# schematic.net
KiCad netlist of a schematic drawn in EAGLE
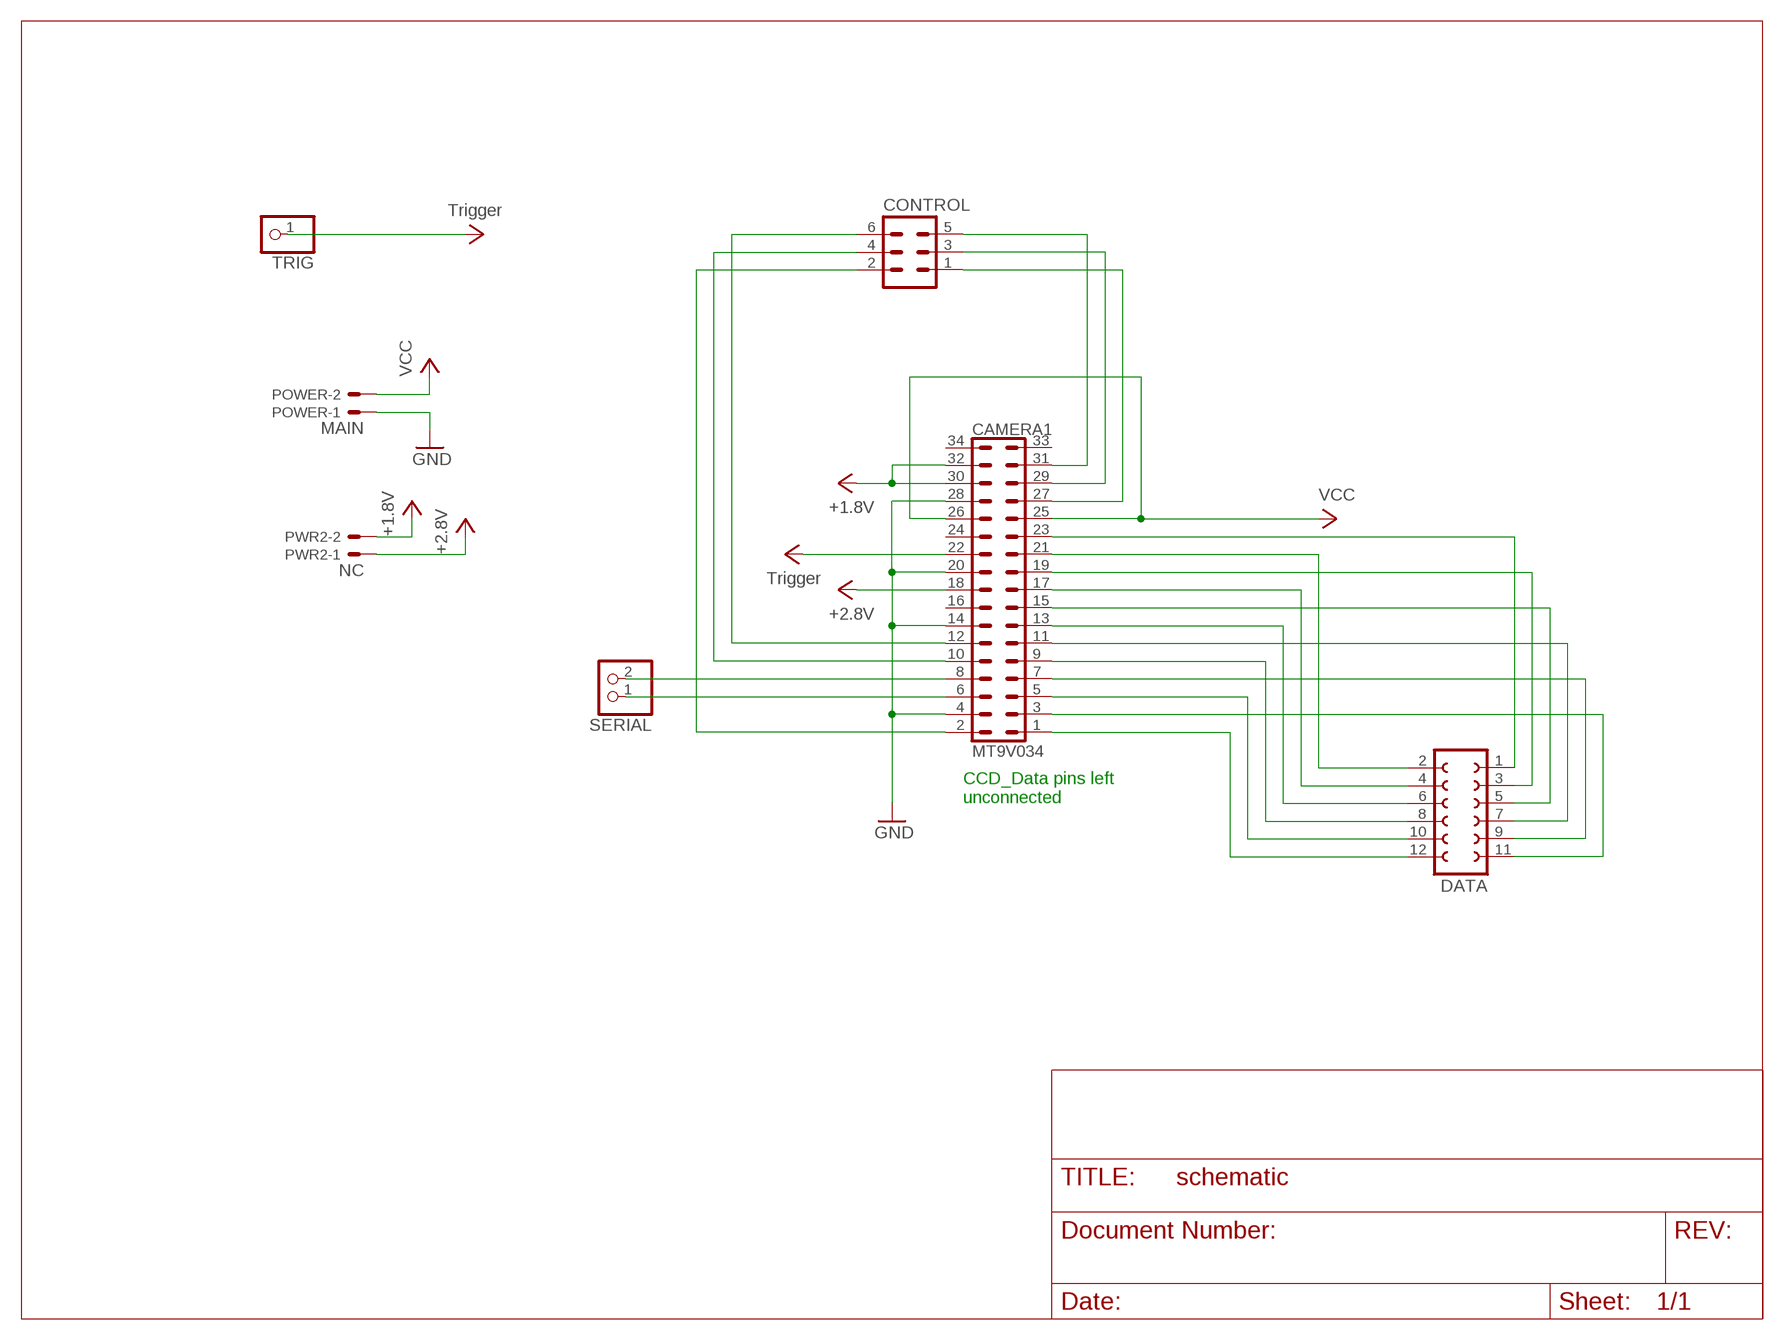
[diagram p0: schematic, sheet 1]

(export (version "E")
  (design (tool "Eeschema 10.0.6"))
  (components
    (comp (ref "CAMERA1")
      (value "MT9V034")
      (footprint "eagle-import:PHB_1MM27_2X17_SNT")
      (libsource (lib "eagle-import") (part "PHB_1MM27_2X17_SNT"))
    )
    (comp (ref "CONTROL")
      (value "MA03-2")
      (footprint "eagle-import:MA03-2")
      (libsource (lib "eagle-import") (part "MA03-2"))
    )
    (comp (ref "DATA")
      (value "FE06-2")
      (footprint "eagle-import:FE06-2")
      (libsource (lib "eagle-import") (part "FE06-2"))
    )
    (comp (ref "POWER")
      (value "MAIN")
      (footprint "eagle-import:22-23-2021")
      (fields (field (name "MF") "MOLEX") (field (name "MPN") "22-23-2021"))
      (libsource (lib "eagle-import") (part "22-23-2021"))
    )
    (comp (ref "PWR2")
      (value "NC")
      (footprint "eagle-import:22-23-2021")
      (fields (field (name "MF") "MOLEX") (field (name "MPN") "22-23-2021"))
      (libsource (lib "eagle-import") (part "22-23-2021"))
    )
    (comp (ref "SERIAL")
      (value "PINHD-1X2")
      (footprint "eagle-import:1X02")
      (libsource (lib "eagle-import") (part "PINHD-1X2"))
    )
    (comp (ref "TRIG")
      (value "PINHD-1X1")
      (footprint "eagle-import:1X01")
      (libsource (lib "eagle-import") (part "PINHD-1X1"))
    )
  )
  (nets
    (net (code "1") (name "+1.8V") (class "Default")
      (node (ref "CAMERA1") (pin "30") (pinfunction "30_30") (pintype "passive"))
      (node (ref "CAMERA1") (pin "32") (pinfunction "32_32") (pintype "passive"))
      (node (ref "PWR2") (pin "2") (pinfunction "S_2") (pintype "passive"))
    )
    (net (code "2") (name "+2.8V") (class "Default")
      (node (ref "CAMERA1") (pin "18") (pinfunction "18_18") (pintype "passive"))
      (node (ref "PWR2") (pin "1") (pinfunction "S_1") (pintype "passive"))
    )
    (net (code "3") (name "GND") (class "Default")
      (node (ref "CAMERA1") (pin "14") (pinfunction "14_14") (pintype "passive"))
      (node (ref "CAMERA1") (pin "20") (pinfunction "20_20") (pintype "passive"))
      (node (ref "CAMERA1") (pin "28") (pinfunction "28_28") (pintype "passive"))
      (node (ref "CAMERA1") (pin "4") (pinfunction "4_4") (pintype "passive"))
      (node (ref "POWER") (pin "1") (pinfunction "S_1") (pintype "passive"))
    )
    (net (code "4") (name "Net-(CAMERA1-Pad1)") (class "Default")
      (node (ref "CAMERA1") (pin "1") (pinfunction "1_1") (pintype "passive"))
      (node (ref "DATA") (pin "12") (pinfunction "12_12") (pintype "passive"))
    )
    (net (code "5") (name "Net-(CAMERA1-Pad2)") (class "Default")
      (node (ref "CAMERA1") (pin "2") (pinfunction "2_2") (pintype "passive"))
      (node (ref "CONTROL") (pin "2") (pinfunction "2_2") (pintype "passive"))
    )
    (net (code "6") (name "Net-(CAMERA1-Pad3)") (class "Default")
      (node (ref "CAMERA1") (pin "3") (pinfunction "3_3") (pintype "passive"))
      (node (ref "DATA") (pin "11") (pinfunction "11_11") (pintype "passive"))
    )
    (net (code "7") (name "Net-(CAMERA1-Pad5)") (class "Default")
      (node (ref "CAMERA1") (pin "5") (pinfunction "5_5") (pintype "passive"))
      (node (ref "DATA") (pin "10") (pinfunction "10_10") (pintype "passive"))
    )
    (net (code "8") (name "Net-(CAMERA1-Pad6)") (class "Default")
      (node (ref "CAMERA1") (pin "6") (pinfunction "6_6") (pintype "passive"))
      (node (ref "SERIAL") (pin "1") (pinfunction "1_1") (pintype "passive"))
    )
    (net (code "9") (name "Net-(CAMERA1-Pad7)") (class "Default")
      (node (ref "CAMERA1") (pin "7") (pinfunction "7_7") (pintype "passive"))
      (node (ref "DATA") (pin "9") (pinfunction "9_9") (pintype "passive"))
    )
    (net (code "10") (name "Net-(CAMERA1-Pad8)") (class "Default")
      (node (ref "CAMERA1") (pin "8") (pinfunction "8_8") (pintype "passive"))
      (node (ref "SERIAL") (pin "2") (pinfunction "2_2") (pintype "passive"))
    )
    (net (code "11") (name "Net-(CAMERA1-Pad9)") (class "Default")
      (node (ref "CAMERA1") (pin "9") (pinfunction "9_9") (pintype "passive"))
      (node (ref "DATA") (pin "8") (pinfunction "8_8") (pintype "passive"))
    )
    (net (code "12") (name "Net-(CAMERA1-Pad10)") (class "Default")
      (node (ref "CAMERA1") (pin "10") (pinfunction "10_10") (pintype "passive"))
      (node (ref "CONTROL") (pin "4") (pinfunction "4_4") (pintype "passive"))
    )
    (net (code "13") (name "Net-(CAMERA1-Pad11)") (class "Default")
      (node (ref "CAMERA1") (pin "11") (pinfunction "11_11") (pintype "passive"))
      (node (ref "DATA") (pin "7") (pinfunction "7_7") (pintype "passive"))
    )
    (net (code "14") (name "Net-(CAMERA1-Pad12)") (class "Default")
      (node (ref "CAMERA1") (pin "12") (pinfunction "12_12") (pintype "passive"))
      (node (ref "CONTROL") (pin "6") (pinfunction "6_6") (pintype "passive"))
    )
    (net (code "15") (name "Net-(CAMERA1-Pad13)") (class "Default")
      (node (ref "CAMERA1") (pin "13") (pinfunction "13_13") (pintype "passive"))
      (node (ref "DATA") (pin "6") (pinfunction "6_6") (pintype "passive"))
    )
    (net (code "16") (name "Net-(CAMERA1-Pad15)") (class "Default")
      (node (ref "CAMERA1") (pin "15") (pinfunction "15_15") (pintype "passive"))
      (node (ref "DATA") (pin "5") (pinfunction "5_5") (pintype "passive"))
    )
    (net (code "17") (name "Net-(CAMERA1-Pad17)") (class "Default")
      (node (ref "CAMERA1") (pin "17") (pinfunction "17_17") (pintype "passive"))
      (node (ref "DATA") (pin "4") (pinfunction "4_4") (pintype "passive"))
    )
    (net (code "18") (name "Net-(CAMERA1-Pad19)") (class "Default")
      (node (ref "CAMERA1") (pin "19") (pinfunction "19_19") (pintype "passive"))
      (node (ref "DATA") (pin "3") (pinfunction "3_3") (pintype "passive"))
    )
    (net (code "19") (name "Net-(CAMERA1-Pad21)") (class "Default")
      (node (ref "CAMERA1") (pin "21") (pinfunction "21_21") (pintype "passive"))
      (node (ref "DATA") (pin "2") (pinfunction "2_2") (pintype "passive"))
    )
    (net (code "20") (name "Net-(CAMERA1-Pad23)") (class "Default")
      (node (ref "CAMERA1") (pin "23") (pinfunction "23_23") (pintype "passive"))
      (node (ref "DATA") (pin "1") (pinfunction "1_1") (pintype "passive"))
    )
    (net (code "21") (name "Net-(CAMERA1-Pad27)") (class "Default")
      (node (ref "CAMERA1") (pin "27") (pinfunction "27_27") (pintype "passive"))
      (node (ref "CONTROL") (pin "1") (pinfunction "1_1") (pintype "passive"))
    )
    (net (code "22") (name "Net-(CAMERA1-Pad29)") (class "Default")
      (node (ref "CAMERA1") (pin "29") (pinfunction "29_29") (pintype "passive"))
      (node (ref "CONTROL") (pin "3") (pinfunction "3_3") (pintype "passive"))
    )
    (net (code "23") (name "Net-(CAMERA1-Pad31)") (class "Default")
      (node (ref "CAMERA1") (pin "31") (pinfunction "31_31") (pintype "passive"))
      (node (ref "CONTROL") (pin "5") (pinfunction "5_5") (pintype "passive"))
    )
    (net (code "24") (name "Trigger") (class "Default")
      (node (ref "CAMERA1") (pin "22") (pinfunction "22_22") (pintype "passive"))
      (node (ref "TRIG") (pin "1") (pinfunction "1_1") (pintype "passive"))
    )
    (net (code "25") (name "VCC") (class "Default")
      (node (ref "CAMERA1") (pin "25") (pinfunction "25_25") (pintype "passive"))
      (node (ref "CAMERA1") (pin "26") (pinfunction "26_26") (pintype "passive"))
      (node (ref "POWER") (pin "2") (pinfunction "S_2") (pintype "passive"))
    )
    (net (code "26") (name "unconnected-(CAMERA1-Pad16)") (class "Default")
      (node (ref "CAMERA1") (pin "16") (pinfunction "16_16") (pintype "passive"))
    )
    (net (code "27") (name "unconnected-(CAMERA1-Pad24)") (class "Default")
      (node (ref "CAMERA1") (pin "24") (pinfunction "24_24") (pintype "passive"))
    )
    (net (code "28") (name "unconnected-(CAMERA1-Pad33)") (class "Default")
      (node (ref "CAMERA1") (pin "33") (pinfunction "33_33") (pintype "passive"))
    )
    (net (code "29") (name "unconnected-(CAMERA1-Pad34)") (class "Default")
      (node (ref "CAMERA1") (pin "34") (pinfunction "34_34") (pintype "passive"))
    )
  )
)
